# sBoardUS.net
KiCad netlist of a schematic drawn in EAGLE
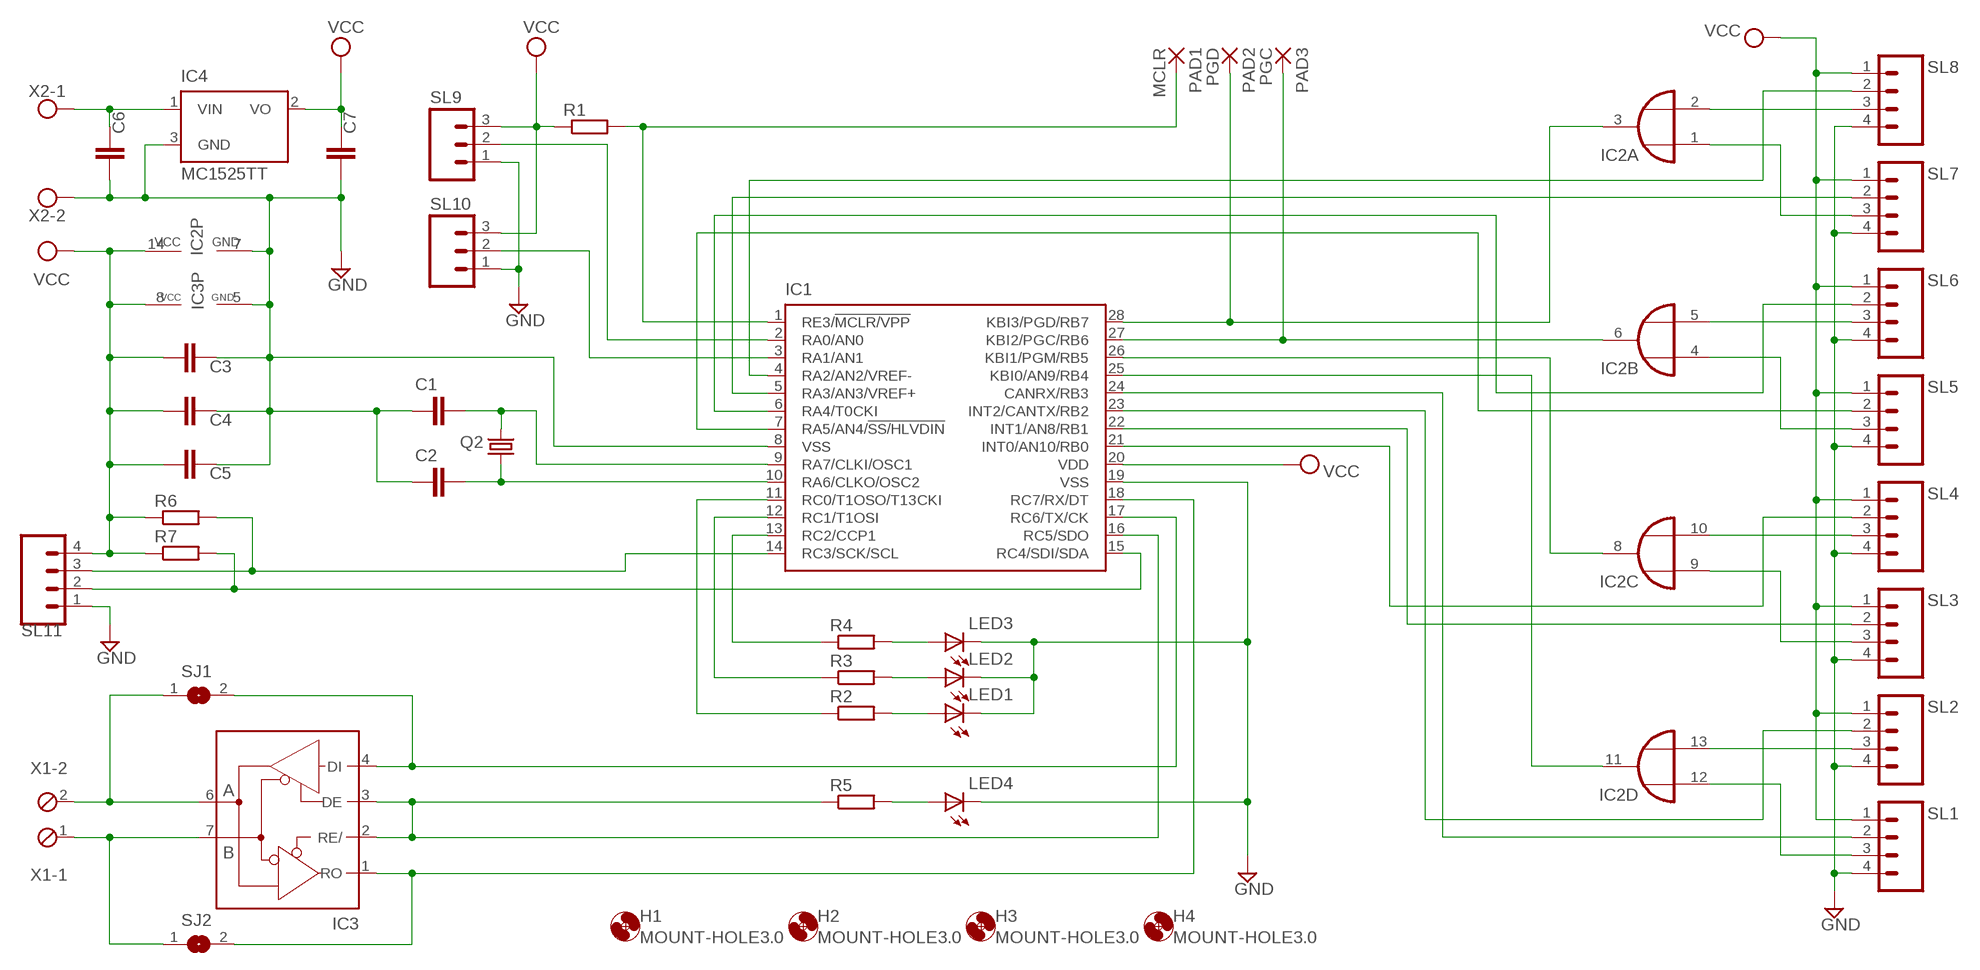
[diagram p0: schematic, sheet 1]

(export (version "E")
  (design (tool "Eeschema 10.0.6"))
  (components
    (comp (ref "C1")
      (value "C-EUC0805")
      (footprint "eagle-import:C0805")
      (libsource (lib "eagle-import") (part "C-EUC0805"))
    )
    (comp (ref "C2")
      (value "C-EUC0805")
      (footprint "eagle-import:C0805")
      (libsource (lib "eagle-import") (part "C-EUC0805"))
    )
    (comp (ref "C3")
      (value "C-EUC0805")
      (footprint "eagle-import:C0805")
      (libsource (lib "eagle-import") (part "C-EUC0805"))
    )
    (comp (ref "C4")
      (value "C-EUC0805")
      (footprint "eagle-import:C0805")
      (libsource (lib "eagle-import") (part "C-EUC0805"))
    )
    (comp (ref "C5")
      (value "C-EUC0805")
      (footprint "eagle-import:C0805")
      (libsource (lib "eagle-import") (part "C-EUC0805"))
    )
    (comp (ref "C6")
      (value "C-EUC0805")
      (footprint "eagle-import:C0805")
      (libsource (lib "eagle-import") (part "C-EUC0805"))
    )
    (comp (ref "C7")
      (value "C-EUC0805")
      (footprint "eagle-import:C0805")
      (libsource (lib "eagle-import") (part "C-EUC0805"))
    )
    (comp (ref "H1")
      (value "MOUNT-HOLE3.0")
      (footprint "eagle-import:3,0")
      (libsource (lib "eagle-import") (part "MOUNT-HOLE3.0"))
    )
    (comp (ref "H2")
      (value "MOUNT-HOLE3.0")
      (footprint "eagle-import:3,0")
      (libsource (lib "eagle-import") (part "MOUNT-HOLE3.0"))
    )
    (comp (ref "H3")
      (value "MOUNT-HOLE3.0")
      (footprint "eagle-import:3,0")
      (libsource (lib "eagle-import") (part "MOUNT-HOLE3.0"))
    )
    (comp (ref "H4")
      (value "MOUNT-HOLE3.0")
      (footprint "eagle-import:3,0")
      (libsource (lib "eagle-import") (part "MOUNT-HOLE3.0"))
    )
    (comp (ref "IC1")
      (value "PIC18F2580-E/SO")
      (footprint "eagle-import:SO28W")
      (fields (field (name "MF") "MICROCHIP") (field (name "MPN") "PIC18F2580-I/SO"))
      (libsource (lib "eagle-import") (part "PIC18F280-E/SO5"))
    )
    (comp (ref "IC2")
      (value "74AC32D")
      (footprint "eagle-import:SO14")
      (libsource (lib "eagle-import") (part "7432DAC"))
    )
    (comp (ref "IC3")
      (value "MAX481CSA")
      (footprint "eagle-import:SO08")
      (fields (field (name "MF") "MAXIM"))
      (libsource (lib "eagle-import") (part "MAX481CSA"))
    )
    (comp (ref "IC4")
      (value "MC1525TT")
      (footprint "eagle-import:SOT23")
      (libsource (lib "eagle-import") (part "MC15TT25"))
    )
    (comp (ref "LED1")
      (value "LED")
      (footprint "eagle-import:SMARTLED-TTW")
      (libsource (lib "eagle-import") (part "LED"))
    )
    (comp (ref "LED2")
      (value "LED")
      (footprint "eagle-import:SMARTLED-TTW")
      (libsource (lib "eagle-import") (part "LED"))
    )
    (comp (ref "LED3")
      (value "LED")
      (footprint "eagle-import:SMARTLED-TTW")
      (libsource (lib "eagle-import") (part "LED"))
    )
    (comp (ref "LED4")
      (value "LED")
      (footprint "eagle-import:SMARTLED-TTW")
      (libsource (lib "eagle-import") (part "LED"))
    )
    (comp (ref "PAD1")
      (value "MCLR")
      (footprint "eagle-import:SMD1,27-2,54")
      (libsource (lib "eagle-import") (part "SMD2"))
    )
    (comp (ref "PAD2")
      (value "PGD")
      (footprint "eagle-import:SMD1,27-2,54")
      (libsource (lib "eagle-import") (part "SMD2"))
    )
    (comp (ref "PAD3")
      (value "PGC")
      (footprint "eagle-import:SMD1,27-2,54")
      (libsource (lib "eagle-import") (part "SMD2"))
    )
    (comp (ref "Q2")
      (value "CRYSTALHC49U-V")
      (footprint "eagle-import:HC49U-V")
      (libsource (lib "eagle-import") (part "CRYSTALHC49U-V"))
    )
    (comp (ref "R1")
      (value "R-EU_R0805")
      (footprint "eagle-import:R0805")
      (libsource (lib "eagle-import") (part "R-EU_R0805"))
    )
    (comp (ref "R2")
      (value "R-EU_R0805")
      (footprint "eagle-import:R0805")
      (libsource (lib "eagle-import") (part "R-EU_R0805"))
    )
    (comp (ref "R3")
      (value "R-EU_R0805")
      (footprint "eagle-import:R0805")
      (libsource (lib "eagle-import") (part "R-EU_R0805"))
    )
    (comp (ref "R4")
      (value "R-EU_R0805")
      (footprint "eagle-import:R0805")
      (libsource (lib "eagle-import") (part "R-EU_R0805"))
    )
    (comp (ref "R5")
      (value "R-EU_R0805")
      (footprint "eagle-import:R0805")
      (libsource (lib "eagle-import") (part "R-EU_R0805"))
    )
    (comp (ref "R6")
      (value "R-EU_R0805")
      (footprint "eagle-import:R0805")
      (libsource (lib "eagle-import") (part "R-EU_R0805"))
    )
    (comp (ref "R7")
      (value "R-EU_R0805")
      (footprint "eagle-import:R0805")
      (libsource (lib "eagle-import") (part "R-EU_R0805"))
    )
    (comp (ref "SJ1") (value "SJ") (footprint "eagle-import:SJ") (libsource (lib "eagle-import") (part "SJ")))
    (comp (ref "SJ2") (value "SJ") (footprint "eagle-import:SJ") (libsource (lib "eagle-import") (part "SJ")))
    (comp (ref "SL1")
      (value "M04")
      (footprint "eagle-import:04P")
      (libsource (lib "eagle-import") (part "M04"))
    )
    (comp (ref "SL2")
      (value "M04")
      (footprint "eagle-import:04P")
      (libsource (lib "eagle-import") (part "M04"))
    )
    (comp (ref "SL3")
      (value "M04")
      (footprint "eagle-import:04P")
      (libsource (lib "eagle-import") (part "M04"))
    )
    (comp (ref "SL4")
      (value "M04")
      (footprint "eagle-import:04P")
      (libsource (lib "eagle-import") (part "M04"))
    )
    (comp (ref "SL5")
      (value "M04")
      (footprint "eagle-import:04P")
      (libsource (lib "eagle-import") (part "M04"))
    )
    (comp (ref "SL6")
      (value "M04")
      (footprint "eagle-import:04P")
      (libsource (lib "eagle-import") (part "M04"))
    )
    (comp (ref "SL7")
      (value "M04")
      (footprint "eagle-import:04P")
      (libsource (lib "eagle-import") (part "M04"))
    )
    (comp (ref "SL8")
      (value "M04")
      (footprint "eagle-import:04P")
      (libsource (lib "eagle-import") (part "M04"))
    )
    (comp (ref "SL9")
      (value "M03")
      (footprint "eagle-import:03P")
      (libsource (lib "eagle-import") (part "M03"))
    )
    (comp (ref "SL10")
      (value "M03")
      (footprint "eagle-import:03P")
      (libsource (lib "eagle-import") (part "M03"))
    )
    (comp (ref "SL11")
      (value "M04")
      (footprint "eagle-import:04P")
      (libsource (lib "eagle-import") (part "M04"))
    )
    (comp (ref "X1")
      (value "MPT2")
      (footprint "eagle-import:2POL254")
      (libsource (lib "eagle-import") (part "MPT2"))
    )
    (comp (ref "X2")
      (value "AK500/2")
      (footprint "eagle-import:AK500_2")
      (libsource (lib "eagle-import") (part "AK500/2"))
    )
  )
  (nets
    (net (code "1") (name "GND") (class "Default")
      (node (ref "C1") (pin "1") (pinfunction "1_1") (pintype "passive"))
      (node (ref "C2") (pin "1") (pinfunction "1_1") (pintype "passive"))
      (node (ref "C3") (pin "1") (pinfunction "1_1") (pintype "passive"))
      (node (ref "C4") (pin "1") (pinfunction "1_1") (pintype "passive"))
      (node (ref "C5") (pin "1") (pinfunction "1_1") (pintype "passive"))
      (node (ref "C6") (pin "2") (pinfunction "2_2") (pintype "passive"))
      (node (ref "C7") (pin "2") (pinfunction "2_2") (pintype "passive"))
      (node (ref "IC1") (pin "19") (pinfunction "VSS_19") (pintype "power_in"))
      (node (ref "IC1") (pin "8") (pinfunction "VSS_8") (pintype "power_in"))
      (node (ref "IC2") (pin "7") (pinfunction "GND_7") (pintype "power_in"))
      (node (ref "IC3") (pin "5") (pinfunction "GND_5") (pintype "power_in"))
      (node (ref "IC4") (pin "3") (pinfunction "GND_3") (pintype "passive"))
      (node (ref "LED1") (pin "C@1") (pinfunction "C_C@1") (pintype "passive"))
      (node (ref "LED2") (pin "C@1") (pinfunction "C_C@1") (pintype "passive"))
      (node (ref "LED3") (pin "C@1") (pinfunction "C_C@1") (pintype "passive"))
      (node (ref "LED4") (pin "C@1") (pinfunction "C_C@1") (pintype "passive"))
      (node (ref "SL1") (pin "4") (pinfunction "4_4") (pintype "passive"))
      (node (ref "SL10") (pin "1") (pinfunction "1_1") (pintype "passive"))
      (node (ref "SL11") (pin "1") (pinfunction "1_1") (pintype "passive"))
      (node (ref "SL2") (pin "4") (pinfunction "4_4") (pintype "passive"))
      (node (ref "SL3") (pin "4") (pinfunction "4_4") (pintype "passive"))
      (node (ref "SL4") (pin "4") (pinfunction "4_4") (pintype "passive"))
      (node (ref "SL5") (pin "4") (pinfunction "4_4") (pintype "passive"))
      (node (ref "SL6") (pin "4") (pinfunction "4_4") (pintype "passive"))
      (node (ref "SL7") (pin "4") (pinfunction "4_4") (pintype "passive"))
      (node (ref "SL8") (pin "4") (pinfunction "4_4") (pintype "passive"))
      (node (ref "SL9") (pin "1") (pinfunction "1_1") (pintype "passive"))
      (node (ref "X2") (pin "2") (pinfunction "KL_2") (pintype "passive"))
    )
    (net (code "2") (name "Net-(IC1-CANRX{slash}RB3)") (class "Default")
      (node (ref "IC1") (pin "24") (pinfunction "CANRX/RB3_24") (pintype "bidirectional"))
      (node (ref "SL1") (pin "2") (pinfunction "2_2") (pintype "passive"))
    )
    (net (code "3") (name "Net-(IC1-INT0{slash}AN10{slash}RB0)") (class "Default")
      (node (ref "IC1") (pin "21") (pinfunction "INT0/AN10/RB0_21") (pintype "bidirectional"))
      (node (ref "SL4") (pin "2") (pinfunction "2_2") (pintype "passive"))
    )
    (net (code "4") (name "Net-(IC1-INT1{slash}AN8{slash}RB1)") (class "Default")
      (node (ref "IC1") (pin "22") (pinfunction "INT1/AN8/RB1_22") (pintype "bidirectional"))
      (node (ref "SL3") (pin "2") (pinfunction "2_2") (pintype "passive"))
    )
    (net (code "5") (name "Net-(IC1-INT2{slash}CANTX{slash}RB2)") (class "Default")
      (node (ref "IC1") (pin "23") (pinfunction "INT2/CANTX/RB2_23") (pintype "bidirectional"))
      (node (ref "SL2") (pin "2") (pinfunction "2_2") (pintype "passive"))
    )
    (net (code "6") (name "Net-(IC1-KBI0{slash}AN9{slash}RB4)") (class "Default")
      (node (ref "IC1") (pin "25") (pinfunction "KBI0/AN9/RB4_25") (pintype "bidirectional"))
      (node (ref "IC2") (pin "11") (pinfunction "O_11") (pintype "output"))
    )
    (net (code "7") (name "Net-(IC1-KBI1{slash}PGM{slash}RB5)") (class "Default")
      (node (ref "IC1") (pin "26") (pinfunction "KBI1/PGM/RB5_26") (pintype "bidirectional"))
      (node (ref "IC2") (pin "8") (pinfunction "O_8") (pintype "output"))
    )
    (net (code "8") (name "Net-(IC1-KBI2{slash}PGC{slash}RB6)") (class "Default")
      (node (ref "IC1") (pin "27") (pinfunction "KBI2/PGC/RB6_27") (pintype "bidirectional"))
      (node (ref "IC2") (pin "6") (pinfunction "O_6") (pintype "output"))
      (node (ref "PAD3") (pin "1") (pinfunction "P_1") (pintype "passive"))
    )
    (net (code "9") (name "Net-(IC1-KBI3{slash}PGD{slash}RB7)") (class "Default")
      (node (ref "IC1") (pin "28") (pinfunction "KBI3/PGD/RB7_28") (pintype "bidirectional"))
      (node (ref "IC2") (pin "3") (pinfunction "O_3") (pintype "output"))
      (node (ref "PAD2") (pin "1") (pinfunction "P_1") (pintype "passive"))
    )
    (net (code "10") (name "Net-(IC1-RA0{slash}AN0)") (class "Default")
      (node (ref "IC1") (pin "2") (pinfunction "RA0/AN0_2") (pintype "bidirectional"))
      (node (ref "SL9") (pin "2") (pinfunction "2_2") (pintype "passive"))
    )
    (net (code "11") (name "Net-(IC1-RA1{slash}AN1)") (class "Default")
      (node (ref "IC1") (pin "3") (pinfunction "RA1/AN1_3") (pintype "bidirectional"))
      (node (ref "SL10") (pin "2") (pinfunction "2_2") (pintype "passive"))
    )
    (net (code "12") (name "Net-(IC1-RA2{slash}AN2{slash}VREF-)") (class "Default")
      (node (ref "IC1") (pin "4") (pinfunction "RA2/AN2/VREF-_4") (pintype "bidirectional"))
      (node (ref "SL8") (pin "2") (pinfunction "2_2") (pintype "passive"))
    )
    (net (code "13") (name "Net-(IC1-RA3{slash}AN3{slash}VREF+)") (class "Default")
      (node (ref "IC1") (pin "5") (pinfunction "RA3/AN3/VREF+_5") (pintype "bidirectional"))
      (node (ref "SL7") (pin "2") (pinfunction "2_2") (pintype "passive"))
    )
    (net (code "14") (name "Net-(IC1-RA4{slash}T0CKI)") (class "Default")
      (node (ref "IC1") (pin "6") (pinfunction "RA4/T0CKI_6") (pintype "bidirectional"))
      (node (ref "SL6") (pin "2") (pinfunction "2_2") (pintype "passive"))
    )
    (net (code "15") (name "Net-(IC1-RA5{slash}AN4{slash}~{SS{slash}HLVDIN})") (class "Default")
      (node (ref "IC1") (pin "7") (pinfunction "RA5/AN4/~{SS/HLVDIN}_7") (pintype "bidirectional"))
      (node (ref "SL5") (pin "2") (pinfunction "2_2") (pintype "passive"))
    )
    (net (code "16") (name "Net-(IC1-RA6{slash}CLKO{slash}OSC2)") (class "Default")
      (node (ref "C2") (pin "2") (pinfunction "2_2") (pintype "passive"))
      (node (ref "IC1") (pin "10") (pinfunction "RA6/CLKO/OSC2_10") (pintype "output"))
      (node (ref "Q2") (pin "1") (pinfunction "1_1") (pintype "passive"))
    )
    (net (code "17") (name "Net-(IC1-RA7{slash}CLKI{slash}OSC1)") (class "Default")
      (node (ref "C1") (pin "2") (pinfunction "2_2") (pintype "passive"))
      (node (ref "IC1") (pin "9") (pinfunction "RA7/CLKI/OSC1_9") (pintype "input"))
      (node (ref "Q2") (pin "2") (pinfunction "2_2") (pintype "passive"))
    )
    (net (code "18") (name "Net-(IC1-RC0{slash}T1OSO{slash}T13CKI)") (class "Default")
      (node (ref "IC1") (pin "11") (pinfunction "RC0/T1OSO/T13CKI_11") (pintype "bidirectional"))
      (node (ref "R2") (pin "1") (pinfunction "1_1") (pintype "passive"))
    )
    (net (code "19") (name "Net-(IC1-RC1{slash}T1OSI)") (class "Default")
      (node (ref "IC1") (pin "12") (pinfunction "RC1/T1OSI_12") (pintype "bidirectional"))
      (node (ref "R3") (pin "1") (pinfunction "1_1") (pintype "passive"))
    )
    (net (code "20") (name "Net-(IC1-RC2{slash}CCP1)") (class "Default")
      (node (ref "IC1") (pin "13") (pinfunction "RC2/CCP1_13") (pintype "bidirectional"))
      (node (ref "R4") (pin "1") (pinfunction "1_1") (pintype "passive"))
    )
    (net (code "21") (name "Net-(IC1-RC3{slash}SCK{slash}SCL)") (class "Default")
      (node (ref "IC1") (pin "14") (pinfunction "RC3/SCK/SCL_14") (pintype "bidirectional"))
      (node (ref "R6") (pin "2") (pinfunction "2_2") (pintype "passive"))
      (node (ref "SL11") (pin "3") (pinfunction "3_3") (pintype "passive"))
    )
    (net (code "22") (name "Net-(IC1-RC4{slash}SDI{slash}SDA)") (class "Default")
      (node (ref "IC1") (pin "15") (pinfunction "RC4/SDI/SDA_15") (pintype "bidirectional"))
      (node (ref "R7") (pin "2") (pinfunction "2_2") (pintype "passive"))
      (node (ref "SL11") (pin "2") (pinfunction "2_2") (pintype "passive"))
    )
    (net (code "23") (name "Net-(IC1-RC5{slash}SDO)") (class "Default")
      (node (ref "IC1") (pin "16") (pinfunction "RC5/SDO_16") (pintype "bidirectional"))
      (node (ref "IC3") (pin "2") (pinfunction "RE/_2") (pintype "input"))
      (node (ref "IC3") (pin "3") (pinfunction "DE_3") (pintype "input"))
      (node (ref "R5") (pin "1") (pinfunction "1_1") (pintype "passive"))
    )
    (net (code "24") (name "Net-(IC1-RC6{slash}TX{slash}CK)") (class "Default")
      (node (ref "IC1") (pin "17") (pinfunction "RC6/TX/CK_17") (pintype "bidirectional"))
      (node (ref "IC3") (pin "4") (pinfunction "DI_4") (pintype "input"))
      (node (ref "SJ1") (pin "2") (pinfunction "2_2") (pintype "passive"))
    )
    (net (code "25") (name "Net-(IC1-RC7{slash}RX{slash}DT)") (class "Default")
      (node (ref "IC1") (pin "18") (pinfunction "RC7/RX/DT_18") (pintype "bidirectional"))
      (node (ref "IC3") (pin "1") (pinfunction "RO_1") (pintype "output"))
      (node (ref "SJ2") (pin "2") (pinfunction "2_2") (pintype "passive"))
    )
    (net (code "26") (name "Net-(IC1-RE3{slash}~{MCLR{slash}VPP})") (class "Default")
      (node (ref "IC1") (pin "1") (pinfunction "RE3/~{MCLR/VPP}_1") (pintype "input"))
      (node (ref "PAD1") (pin "1") (pinfunction "P_1") (pintype "passive"))
      (node (ref "R1") (pin "2") (pinfunction "2_2") (pintype "passive"))
    )
    (net (code "27") (name "Net-(IC2A-I0)") (class "Default")
      (node (ref "IC2") (pin "1") (pinfunction "I0_1") (pintype "input"))
      (node (ref "SL7") (pin "3") (pinfunction "3_3") (pintype "passive"))
    )
    (net (code "28") (name "Net-(IC2A-I1)") (class "Default")
      (node (ref "IC2") (pin "2") (pinfunction "I1_2") (pintype "input"))
      (node (ref "SL8") (pin "3") (pinfunction "3_3") (pintype "passive"))
    )
    (net (code "29") (name "Net-(IC2B-I0)") (class "Default")
      (node (ref "IC2") (pin "4") (pinfunction "I0_4") (pintype "input"))
      (node (ref "SL5") (pin "3") (pinfunction "3_3") (pintype "passive"))
    )
    (net (code "30") (name "Net-(IC2B-I1)") (class "Default")
      (node (ref "IC2") (pin "5") (pinfunction "I1_5") (pintype "input"))
      (node (ref "SL6") (pin "3") (pinfunction "3_3") (pintype "passive"))
    )
    (net (code "31") (name "Net-(IC2C-I0)") (class "Default")
      (node (ref "IC2") (pin "9") (pinfunction "I0_9") (pintype "input"))
      (node (ref "SL3") (pin "3") (pinfunction "3_3") (pintype "passive"))
    )
    (net (code "32") (name "Net-(IC2C-I1)") (class "Default")
      (node (ref "IC2") (pin "10") (pinfunction "I1_10") (pintype "input"))
      (node (ref "SL4") (pin "3") (pinfunction "3_3") (pintype "passive"))
    )
    (net (code "33") (name "Net-(IC2D-I0)") (class "Default")
      (node (ref "IC2") (pin "12") (pinfunction "I0_12") (pintype "input"))
      (node (ref "SL1") (pin "3") (pinfunction "3_3") (pintype "passive"))
    )
    (net (code "34") (name "Net-(IC2D-I1)") (class "Default")
      (node (ref "IC2") (pin "13") (pinfunction "I1_13") (pintype "input"))
      (node (ref "SL2") (pin "3") (pinfunction "3_3") (pintype "passive"))
    )
    (net (code "35") (name "Net-(IC3A-A)") (class "Default")
      (node (ref "IC3") (pin "6") (pinfunction "A_6") (pintype "passive"))
      (node (ref "SJ1") (pin "1") (pinfunction "1_1") (pintype "passive"))
      (node (ref "X1") (pin "2") (pinfunction "1_2") (pintype "passive"))
    )
    (net (code "36") (name "Net-(IC3A-B)") (class "Default")
      (node (ref "IC3") (pin "7") (pinfunction "B_7") (pintype "passive"))
      (node (ref "SJ2") (pin "1") (pinfunction "1_1") (pintype "passive"))
      (node (ref "X1") (pin "1") (pinfunction "1_1") (pintype "passive"))
    )
    (net (code "37") (name "Net-(IC4-VIN)") (class "Default")
      (node (ref "C6") (pin "1") (pinfunction "1_1") (pintype "passive"))
      (node (ref "IC4") (pin "1") (pinfunction "VIN_1") (pintype "input"))
      (node (ref "X2") (pin "1") (pinfunction "KL_1") (pintype "passive"))
    )
    (net (code "38") (name "Net-(LED1-A)") (class "Default")
      (node (ref "LED1") (pin "A@1") (pinfunction "A_A@1") (pintype "passive"))
      (node (ref "R2") (pin "2") (pinfunction "2_2") (pintype "passive"))
    )
    (net (code "39") (name "Net-(LED2-A)") (class "Default")
      (node (ref "LED2") (pin "A@1") (pinfunction "A_A@1") (pintype "passive"))
      (node (ref "R3") (pin "2") (pinfunction "2_2") (pintype "passive"))
    )
    (net (code "40") (name "Net-(LED3-A)") (class "Default")
      (node (ref "LED3") (pin "A@1") (pinfunction "A_A@1") (pintype "passive"))
      (node (ref "R4") (pin "2") (pinfunction "2_2") (pintype "passive"))
    )
    (net (code "41") (name "Net-(LED4-A)") (class "Default")
      (node (ref "LED4") (pin "A@1") (pinfunction "A_A@1") (pintype "passive"))
      (node (ref "R5") (pin "2") (pinfunction "2_2") (pintype "passive"))
    )
    (net (code "42") (name "VCC") (class "Default")
      (node (ref "C3") (pin "2") (pinfunction "2_2") (pintype "passive"))
      (node (ref "C4") (pin "2") (pinfunction "2_2") (pintype "passive"))
      (node (ref "C5") (pin "2") (pinfunction "2_2") (pintype "passive"))
      (node (ref "C7") (pin "1") (pinfunction "1_1") (pintype "passive"))
      (node (ref "IC1") (pin "20") (pinfunction "VDD_20") (pintype "power_in"))
      (node (ref "IC2") (pin "14") (pinfunction "VCC_14") (pintype "power_in"))
      (node (ref "IC3") (pin "8") (pinfunction "VCC_8") (pintype "power_in"))
      (node (ref "IC4") (pin "2") (pinfunction "VO_2") (pintype "output"))
      (node (ref "R1") (pin "1") (pinfunction "1_1") (pintype "passive"))
      (node (ref "R6") (pin "1") (pinfunction "1_1") (pintype "passive"))
      (node (ref "R7") (pin "1") (pinfunction "1_1") (pintype "passive"))
      (node (ref "SL1") (pin "1") (pinfunction "1_1") (pintype "passive"))
      (node (ref "SL10") (pin "3") (pinfunction "3_3") (pintype "passive"))
      (node (ref "SL11") (pin "4") (pinfunction "4_4") (pintype "passive"))
      (node (ref "SL2") (pin "1") (pinfunction "1_1") (pintype "passive"))
      (node (ref "SL3") (pin "1") (pinfunction "1_1") (pintype "passive"))
      (node (ref "SL4") (pin "1") (pinfunction "1_1") (pintype "passive"))
      (node (ref "SL5") (pin "1") (pinfunction "1_1") (pintype "passive"))
      (node (ref "SL6") (pin "1") (pinfunction "1_1") (pintype "passive"))
      (node (ref "SL7") (pin "1") (pinfunction "1_1") (pintype "passive"))
      (node (ref "SL8") (pin "1") (pinfunction "1_1") (pintype "passive"))
      (node (ref "SL9") (pin "3") (pinfunction "3_3") (pintype "passive"))
    )
  )
)
